# TC264Driver.net
KiCad netlist of a schematic drawn in Altium Designer
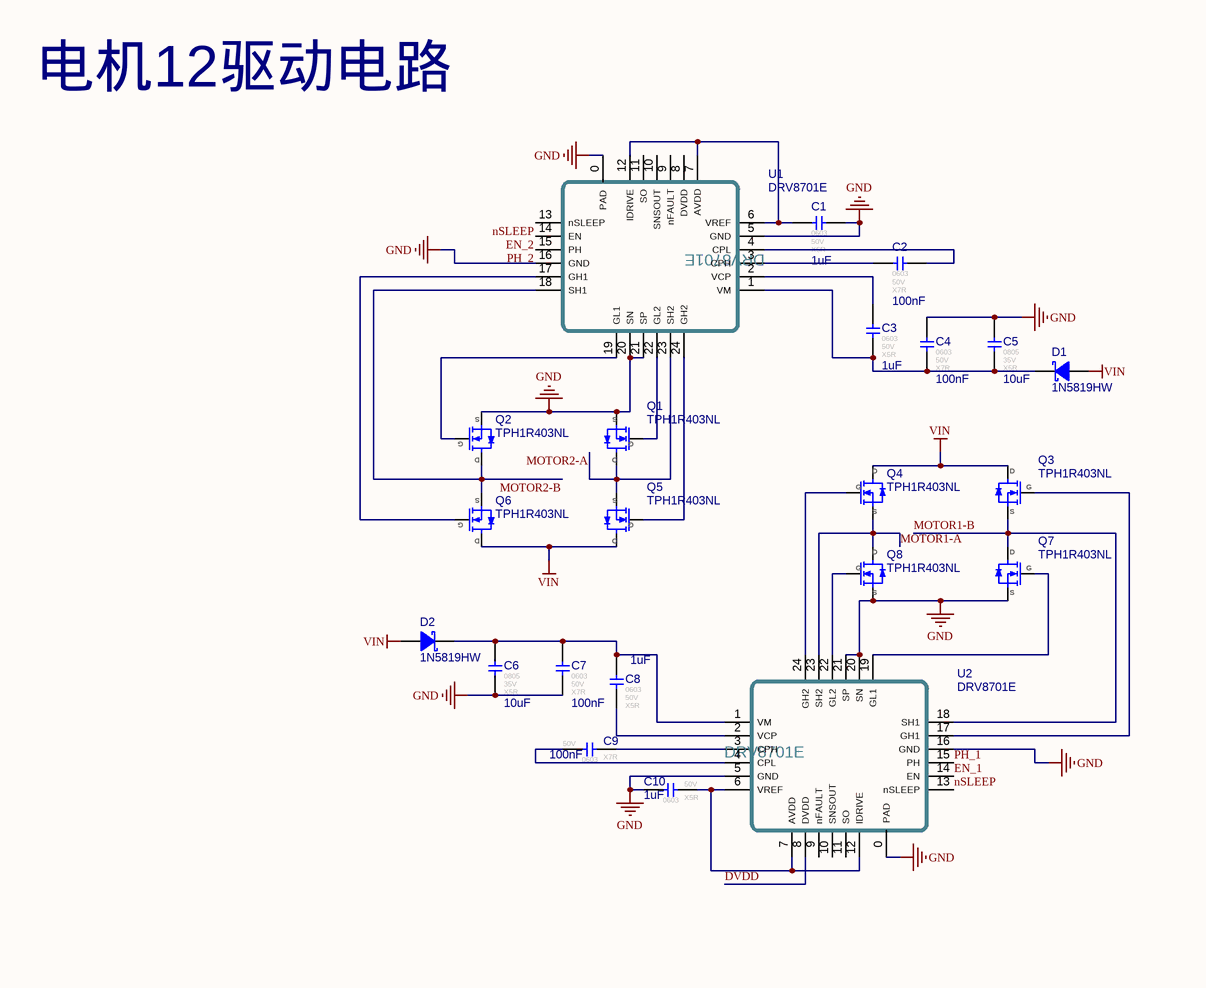
[diagram p0: TC264Driver.SchDoc, top left]
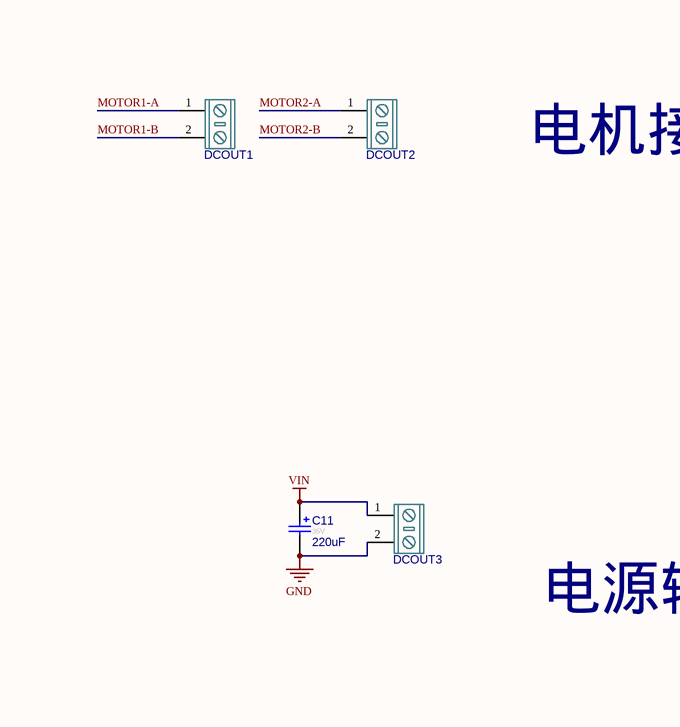
[diagram p1: TC264Driver.SchDoc, top right]
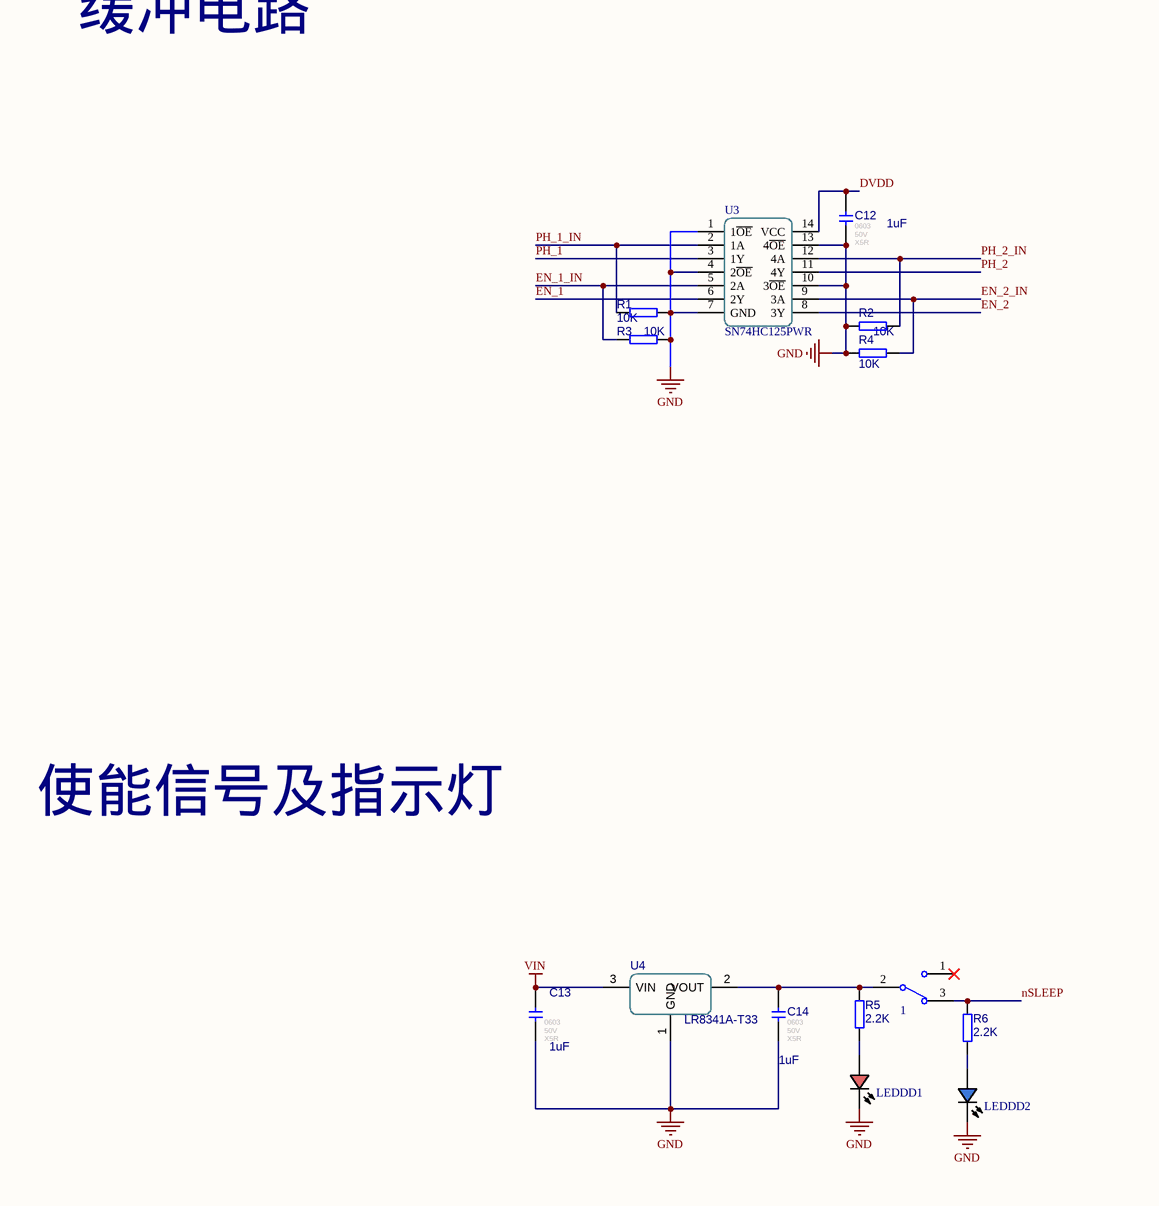
[diagram p2: TC264Driver.SchDoc, bottom left]
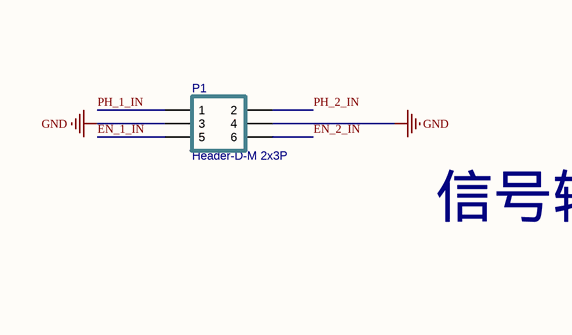
[diagram p3: TC264Driver.SchDoc, bottom right]

(export (version "E")
  (design (tool "Eeschema 10.0.6"))
  (components
    (comp (ref "1")
      (value "SW-SPDT")
      (footprint "SS12D10")
      (description "单刀双掷开关 3脚船型、钮子、拨动开关 SPDT Subminiature Toggle Switch")
      (fields (field (name "PUBLISHER") "Altium Limited"))
      (libsource (lib "TC264") (part "SW-SPDT_1"))
    )
    (comp (ref "C1")
      (value "1uF")
      (footprint "0603")
      (description "贴片瓷片电容; MLCC; 0603(1608);")
      (fields
        (field (name "VOLTAGE") "50V")
        (field (name "TYPE") "X5R")
        (field (name "Comment") "1uF 50V X5R")
      )
      (libsource (lib "TC264") (part "1uF 0603 50V X5R"))
    )
    (comp (ref "C2")
      (value "100nF")
      (footprint "0603")
      (description "贴片瓷片电容; MLCC; 0603(1608);")
      (fields
        (field (name "VOLTAGE") "50V")
        (field (name "TYPE") "X7R")
        (field (name "Comment") "100nF 50V X7R")
      )
      (libsource (lib "TC264") (part "100nF 0603 50V X7R"))
    )
    (comp (ref "C3")
      (value "1uF")
      (footprint "0603")
      (description "贴片瓷片电容; MLCC; 0603(1608);")
      (fields
        (field (name "VOLTAGE") "50V")
        (field (name "TYPE") "X5R")
        (field (name "Comment") "1uF 50V X5R")
      )
      (libsource (lib "TC264") (part "1uF 0603 50V X5R"))
    )
    (comp (ref "C4")
      (value "100nF")
      (footprint "0603")
      (description "贴片瓷片电容; MLCC; 0603(1608);")
      (fields
        (field (name "VOLTAGE") "50V")
        (field (name "TYPE") "X7R")
        (field (name "Comment") "100nF 50V X7R")
      )
      (libsource (lib "TC264") (part "100nF 0603 50V X7R"))
    )
    (comp (ref "C5")
      (value "10uF")
      (footprint "0805")
      (description "贴片瓷片电容; MLCC; 0805(2012);")
      (fields
        (field (name "VOLTAGE") "35V")
        (field (name "TYPE") "X5R")
        (field (name "Comment") "10uF 35V X5R")
      )
      (libsource (lib "TC264") (part "10uF 0805 35V X5R"))
    )
    (comp (ref "C6")
      (value "10uF")
      (footprint "0805")
      (description "贴片瓷片电容; MLCC; 0805(2012);")
      (fields
        (field (name "VOLTAGE") "35V")
        (field (name "TYPE") "X5R")
        (field (name "Comment") "10uF 35V X5R")
      )
      (libsource (lib "TC264") (part "10uF 0805 35V X5R"))
    )
    (comp (ref "C7")
      (value "100nF")
      (footprint "0603")
      (description "贴片瓷片电容; MLCC; 0603(1608);")
      (fields
        (field (name "VOLTAGE") "50V")
        (field (name "TYPE") "X7R")
        (field (name "Comment") "100nF 50V X7R")
      )
      (libsource (lib "TC264") (part "100nF 0603 50V X7R"))
    )
    (comp (ref "C8")
      (value "1uF")
      (footprint "0603")
      (description "贴片瓷片电容; MLCC; 0603(1608);")
      (fields
        (field (name "VOLTAGE") "50V")
        (field (name "TYPE") "X5R")
        (field (name "Comment") "1uF 50V X5R")
      )
      (libsource (lib "TC264") (part "1uF 0603 50V X5R"))
    )
    (comp (ref "C9")
      (value "100nF")
      (footprint "0603")
      (description "贴片瓷片电容; MLCC; 0603(1608);")
      (fields
        (field (name "VOLTAGE") "50V")
        (field (name "TYPE") "X7R")
        (field (name "Comment") "100nF 50V X7R")
      )
      (libsource (lib "TC264") (part "100nF 0603 50V X7R"))
    )
    (comp (ref "C10")
      (value "1uF")
      (footprint "0603")
      (description "贴片瓷片电容; MLCC; 0603(1608);")
      (fields
        (field (name "VOLTAGE") "50V")
        (field (name "TYPE") "X5R")
        (field (name "Comment") "1uF 50V X5R")
      )
      (libsource (lib "TC264") (part "1uF 0603 50V X5R"))
    )
    (comp (ref "C11")
      (value "220uF")
      (footprint "Cap-S-D 3.5-8x11.5")
      (description "直插固态电容 220uF 35V 8x12")
      (fields (field (name "VOLTAGE") "35V") (field (name "Comment") "220uF 35V 聚合物固态"))
      (libsource (lib "TC264") (part "S-D 220uF 35V 8x12"))
    )
    (comp (ref "C12")
      (value "1uF")
      (footprint "0603")
      (description "贴片瓷片电容; MLCC; 0603(1608);")
      (fields
        (field (name "VOLTAGE") "50V")
        (field (name "TYPE") "X5R")
        (field (name "Comment") "1uF 50V X5R")
      )
      (libsource (lib "TC264") (part "1uF 0603 50V X5R"))
    )
    (comp (ref "C13")
      (value "1uF")
      (footprint "0603")
      (description "贴片瓷片电容; MLCC; 0603(1608);")
      (fields
        (field (name "VOLTAGE") "50V")
        (field (name "TYPE") "X5R")
        (field (name "Comment") "1uF 50V X5R")
      )
      (libsource (lib "TC264") (part "1uF 0603 50V X5R"))
    )
    (comp (ref "C14")
      (value "1uF")
      (footprint "0603")
      (description "贴片瓷片电容; MLCC; 0603(1608);")
      (fields
        (field (name "VOLTAGE") "50V")
        (field (name "TYPE") "X5R")
        (field (name "Comment") "1uF 50V X5R")
      )
      (libsource (lib "TC264") (part "1uF 0603 50V X5R"))
    )
    (comp (ref "D1")
      (value "1N5819HW")
      (footprint "SOD-123-L")
      (description "1N5819HW 肖特基二极管")
      (libsource (lib "TC264") (part "1N5819HW"))
    )
    (comp (ref "D2")
      (value "1N5819HW")
      (footprint "SOD-123-L")
      (description "1N5819HW 肖特基二极管")
      (libsource (lib "TC264") (part "1N5819HW"))
    )
    (comp (ref "DCOUT1")
      (value "KF/WJ/DG 30x connecter")
      (footprint "KF/WJ/DG 301-2p-5.0mm")
      (description "接线端子 2Pin")
      (libsource (lib "TC264") (part "KF/WJ/DG 30x"))
    )
    (comp (ref "DCOUT2")
      (value "KF/WJ/DG 30x connecter")
      (footprint "KF/WJ/DG 301-2p-5.0mm")
      (description "接线端子 2Pin")
      (libsource (lib "TC264") (part "KF/WJ/DG 30x"))
    )
    (comp (ref "DCOUT3")
      (value "KF/WJ/DG 30x connecter")
      (footprint "KF/WJ/DG 301-2p-5.0mm")
      (description "接线端子 2Pin")
      (libsource (lib "TC264") (part "KF/WJ/DG 30x"))
    )
    (comp (ref "LEDDD1")
      (value "红色贴片LED")
      (footprint "LEDC1608(0603)-L")
      (fields (field (name "PUBLISHER") "Altium Limited"))
      (libsource (lib "TC264") (part "LED Chip Red"))
    )
    (comp (ref "LEDDD2")
      (value "蓝色贴片LED")
      (footprint "LEDC1608(0603)-L")
      (fields (field (name "PUBLISHER") "Altium Limited"))
      (libsource (lib "TC264") (part "LED Chip Blue"))
    )
    (comp (ref "P1")
      (value "Header-D-M 2x3P")
      (footprint "HDR2X3-M")
      (description "2x3pin, 直插, 双排针")
      (libsource (lib "TC264") (part "Header-D-M 2x3P"))
    )
    (comp (ref "Q1")
      (value "TPH1R403NL")
      (footprint "DFN5x6")
      (description "东芝 N沟 MOS")
      (libsource (lib "TC264") (part "TPH1R403NL"))
    )
    (comp (ref "Q2")
      (value "TPH1R403NL")
      (footprint "DFN5x6")
      (description "东芝 N沟 MOS")
      (libsource (lib "TC264") (part "TPH1R403NL"))
    )
    (comp (ref "Q3")
      (value "TPH1R403NL")
      (footprint "DFN5x6")
      (description "东芝 N沟 MOS")
      (libsource (lib "TC264") (part "TPH1R403NL"))
    )
    (comp (ref "Q4")
      (value "TPH1R403NL")
      (footprint "DFN5x6")
      (description "东芝 N沟 MOS")
      (libsource (lib "TC264") (part "TPH1R403NL"))
    )
    (comp (ref "Q5")
      (value "TPH1R403NL")
      (footprint "DFN5x6")
      (description "东芝 N沟 MOS")
      (libsource (lib "TC264") (part "TPH1R403NL"))
    )
    (comp (ref "Q6")
      (value "TPH1R403NL")
      (footprint "DFN5x6")
      (description "东芝 N沟 MOS")
      (libsource (lib "TC264") (part "TPH1R403NL"))
    )
    (comp (ref "Q7")
      (value "TPH1R403NL")
      (footprint "DFN5x6")
      (description "东芝 N沟 MOS")
      (libsource (lib "TC264") (part "TPH1R403NL"))
    )
    (comp (ref "Q8")
      (value "TPH1R403NL")
      (footprint "DFN5x6")
      (description "东芝 N沟 MOS")
      (libsource (lib "TC264") (part "TPH1R403NL"))
    )
    (comp (ref "R1")
      (value "10K")
      (footprint "RESC1608[0603]S-L")
      (description "贴片电阻")
      (fields (field (name "TOLERANCE") "±1%") (field (name "Comment") "10K ±1%"))
      (libsource (lib "TC264") (part "Res-Chip_12"))
    )
    (comp (ref "R2")
      (value "10K")
      (footprint "RESC1608[0603]S-L")
      (description "贴片电阻")
      (fields (field (name "TOLERANCE") "±1%") (field (name "Comment") "10K ±1%"))
      (libsource (lib "TC264") (part "Res-Chip_12"))
    )
    (comp (ref "R3")
      (value "10K")
      (footprint "RESC1608[0603]S-L")
      (description "贴片电阻")
      (fields (field (name "TOLERANCE") "±1%") (field (name "Comment") "10K ±1%"))
      (libsource (lib "TC264") (part "Res-Chip_12"))
    )
    (comp (ref "R4")
      (value "10K")
      (footprint "RESC1608[0603]S-L")
      (description "贴片电阻")
      (fields (field (name "TOLERANCE") "±1%") (field (name "Comment") "10K ±1%"))
      (libsource (lib "TC264") (part "Res-Chip_12"))
    )
    (comp (ref "R5")
      (value "2.2K")
      (footprint "RESC1608[0603]S-L")
      (description "贴片电阻")
      (fields (field (name "TOLERANCE") "±1%") (field (name "Comment") "2.2K ±1%"))
      (libsource (lib "TC264") (part "Res-Chip_1_1"))
    )
    (comp (ref "R6")
      (value "2.2K")
      (footprint "RESC1608[0603]S-L")
      (description "贴片电阻")
      (fields (field (name "TOLERANCE") "±1%") (field (name "Comment") "2.2K ±1%"))
      (libsource (lib "TC264") (part "Res-Chip_1_1"))
    )
    (comp (ref "U1")
      (value "DRV8701E")
      (footprint "QFN24-4x4")
      (description "DRV8701E Ti全桥驱动芯片")
      (libsource (lib "TC264") (part "DRV8701E"))
    )
    (comp (ref "U2")
      (value "DRV8701E")
      (footprint "QFN24-4x4")
      (description "DRV8701E Ti全桥驱动芯片")
      (libsource (lib "TC264") (part "DRV8701E"))
    )
    (comp (ref "U3")
      (value "SN74HC125PWR")
      (footprint "TSSOP-14")
      (description "三态输出的四路缓冲器 TSSOP-20")
      (libsource (lib "TC264") (part "SN74HC125PWR"))
    )
    (comp (ref "U4")
      (value "LR8341A-T33")
      (footprint "SOT-23")
      (description "LDO Vin:40V  Vout:3.3V 100mA ±1% 55dB")
      (libsource (lib "TC264") (part "LR8341A-T33"))
    )
  )
  (nets
    (net (code "1") (name "/DVDD") (class "Default")
      (node (ref "C12") (pin "1") (pinfunction "1_1") (pintype "passive"))
      (node (ref "U2") (pin "8") (pinfunction "DVDD_8") (pintype "passive"))
      (node (ref "U3") (pin "14") (pinfunction "VCC_14") (pintype "passive"))
    )
    (net (code "2") (name "/EN_1") (class "Default")
      (node (ref "U2") (pin "14") (pinfunction "EN_14") (pintype "passive"))
      (node (ref "U3") (pin "6") (pinfunction "2Y_6") (pintype "passive"))
    )
    (net (code "3") (name "/EN_1_IN") (class "Default")
      (node (ref "P1") (pin "5") (pinfunction "5_5") (pintype "passive"))
      (node (ref "R3") (pin "1") (pinfunction "1_1") (pintype "passive"))
      (node (ref "U3") (pin "5") (pinfunction "2A_5") (pintype "passive"))
    )
    (net (code "4") (name "/EN_2") (class "Default")
      (node (ref "U1") (pin "14") (pinfunction "EN_14") (pintype "passive"))
      (node (ref "U3") (pin "8") (pinfunction "3Y_8") (pintype "passive"))
    )
    (net (code "5") (name "/EN_2_IN") (class "Default")
      (node (ref "P1") (pin "6") (pinfunction "6_6") (pintype "passive"))
      (node (ref "R4") (pin "1") (pinfunction "1_1") (pintype "passive"))
      (node (ref "U3") (pin "9") (pinfunction "3A_9") (pintype "passive"))
    )
    (net (code "6") (name "/MOTOR1-A") (class "Default")
      (node (ref "DCOUT1") (pin "1") (pinfunction "1_1") (pintype "passive"))
      (node (ref "Q4") (pin "3") (pinfunction "S_3") (pintype "passive"))
      (node (ref "Q8") (pin "1") (pinfunction "D_1") (pintype "passive"))
      (node (ref "U2") (pin "23") (pinfunction "SH2_23") (pintype "passive"))
    )
    (net (code "7") (name "/MOTOR1-B") (class "Default")
      (node (ref "DCOUT1") (pin "2") (pinfunction "2_2") (pintype "passive"))
      (node (ref "Q3") (pin "3") (pinfunction "S_3") (pintype "passive"))
      (node (ref "Q7") (pin "1") (pinfunction "D_1") (pintype "passive"))
      (node (ref "U2") (pin "18") (pinfunction "SH1_18") (pintype "passive"))
    )
    (net (code "8") (name "/MOTOR2-A") (class "Default")
      (node (ref "DCOUT2") (pin "1") (pinfunction "1_1") (pintype "passive"))
      (node (ref "Q1") (pin "1") (pinfunction "D_1") (pintype "passive"))
      (node (ref "Q5") (pin "3") (pinfunction "S_3") (pintype "passive"))
      (node (ref "U1") (pin "23") (pinfunction "SH2_23") (pintype "passive"))
    )
    (net (code "9") (name "/MOTOR2-B") (class "Default")
      (node (ref "DCOUT2") (pin "2") (pinfunction "2_2") (pintype "passive"))
      (node (ref "Q2") (pin "1") (pinfunction "D_1") (pintype "passive"))
      (node (ref "Q6") (pin "3") (pinfunction "S_3") (pintype "passive"))
      (node (ref "U1") (pin "18") (pinfunction "SH1_18") (pintype "passive"))
    )
    (net (code "10") (name "/PH_1") (class "Default")
      (node (ref "U2") (pin "15") (pinfunction "PH_15") (pintype "passive"))
      (node (ref "U3") (pin "3") (pinfunction "1Y_3") (pintype "passive"))
    )
    (net (code "11") (name "/PH_1_IN") (class "Default")
      (node (ref "P1") (pin "1") (pinfunction "1_1") (pintype "passive"))
      (node (ref "R1") (pin "1") (pinfunction "1_1") (pintype "passive"))
      (node (ref "U3") (pin "2") (pinfunction "1A_2") (pintype "passive"))
    )
    (net (code "12") (name "/PH_2") (class "Default")
      (node (ref "U1") (pin "15") (pinfunction "PH_15") (pintype "passive"))
      (node (ref "U3") (pin "11") (pinfunction "4Y_11") (pintype "passive"))
    )
    (net (code "13") (name "/PH_2_IN") (class "Default")
      (node (ref "P1") (pin "2") (pinfunction "2_2") (pintype "passive"))
      (node (ref "R2") (pin "1") (pinfunction "1_1") (pintype "passive"))
      (node (ref "U3") (pin "12") (pinfunction "4A_12") (pintype "passive"))
    )
    (net (code "14") (name "/nSLEEP") (class "Default")
      (node (ref "1") (pin "3") (pintype "passive"))
      (node (ref "R6") (pin "2") (pinfunction "2_2") (pintype "passive"))
      (node (ref "U1") (pin "13") (pinfunction "nSLEEP_13") (pintype "passive"))
      (node (ref "U2") (pin "13") (pinfunction "nSLEEP_13") (pintype "passive"))
    )
    (net (code "15") (name "GND") (class "Default")
      (node (ref "C1") (pin "2") (pinfunction "2_2") (pintype "passive"))
      (node (ref "C10") (pin "2") (pinfunction "2_2") (pintype "passive"))
      (node (ref "C11") (pin "2") (pinfunction "2_2") (pintype "passive"))
      (node (ref "C12") (pin "2") (pinfunction "2_2") (pintype "passive"))
      (node (ref "C13") (pin "2") (pinfunction "2_2") (pintype "passive"))
      (node (ref "C14") (pin "2") (pinfunction "2_2") (pintype "passive"))
      (node (ref "C4") (pin "1") (pinfunction "1_1") (pintype "passive"))
      (node (ref "C5") (pin "1") (pinfunction "1_1") (pintype "passive"))
      (node (ref "C6") (pin "1") (pinfunction "1_1") (pintype "passive"))
      (node (ref "C7") (pin "1") (pinfunction "1_1") (pintype "passive"))
      (node (ref "DCOUT3") (pin "2") (pinfunction "2_2") (pintype "passive"))
      (node (ref "LEDDD1") (pin "C") (pinfunction "C_C") (pintype "passive"))
      (node (ref "LEDDD2") (pin "C") (pinfunction "C_C") (pintype "passive"))
      (node (ref "P1") (pin "3") (pinfunction "3_3") (pintype "passive"))
      (node (ref "P1") (pin "4") (pinfunction "4_4") (pintype "passive"))
      (node (ref "Q1") (pin "3") (pinfunction "S_3") (pintype "passive"))
      (node (ref "Q2") (pin "3") (pinfunction "S_3") (pintype "passive"))
      (node (ref "Q7") (pin "3") (pinfunction "S_3") (pintype "passive"))
      (node (ref "Q8") (pin "3") (pinfunction "S_3") (pintype "passive"))
      (node (ref "R1") (pin "2") (pinfunction "2_2") (pintype "passive"))
      (node (ref "R2") (pin "2") (pinfunction "2_2") (pintype "passive"))
      (node (ref "R3") (pin "2") (pinfunction "2_2") (pintype "passive"))
      (node (ref "R4") (pin "2") (pinfunction "2_2") (pintype "passive"))
      (node (ref "U1") (pin "0") (pinfunction "PAD_0") (pintype "passive"))
      (node (ref "U1") (pin "16") (pinfunction "GND_16") (pintype "passive"))
      (node (ref "U1") (pin "20") (pinfunction "SN_20") (pintype "passive"))
      (node (ref "U1") (pin "21") (pinfunction "SP_21") (pintype "passive"))
      (node (ref "U1") (pin "5") (pinfunction "GND_5") (pintype "passive"))
      (node (ref "U2") (pin "0") (pinfunction "PAD_0") (pintype "passive"))
      (node (ref "U2") (pin "16") (pinfunction "GND_16") (pintype "passive"))
      (node (ref "U2") (pin "20") (pinfunction "SN_20") (pintype "passive"))
      (node (ref "U2") (pin "21") (pinfunction "SP_21") (pintype "passive"))
      (node (ref "U2") (pin "5") (pinfunction "GND_5") (pintype "passive"))
      (node (ref "U3") (pin "1") (pinfunction "1~{OE}_1") (pintype "passive"))
      (node (ref "U3") (pin "10") (pinfunction "3~{OE}_10") (pintype "passive"))
      (node (ref "U3") (pin "13") (pinfunction "4~{OE}_13") (pintype "passive"))
      (node (ref "U3") (pin "4") (pinfunction "2~{OE}_4") (pintype "passive"))
      (node (ref "U3") (pin "7") (pinfunction "GND_7") (pintype "passive"))
      (node (ref "U4") (pin "1") (pinfunction "GND_1") (pintype "passive"))
    )
    (net (code "16") (name "Net-(LEDDD1-PadA)") (class "Default")
      (node (ref "LEDDD1") (pin "A") (pinfunction "A_A") (pintype "passive"))
      (node (ref "R5") (pin "1") (pinfunction "1_1") (pintype "passive"))
    )
    (net (code "17") (name "Net-(LEDDD2-PadA)") (class "Default")
      (node (ref "LEDDD2") (pin "A") (pinfunction "A_A") (pintype "passive"))
      (node (ref "R6") (pin "1") (pinfunction "1_1") (pintype "passive"))
    )
    (net (code "18") (name "Net-(Q1-G)") (class "Default")
      (node (ref "Q1") (pin "2") (pinfunction "G_2") (pintype "passive"))
      (node (ref "U1") (pin "22") (pinfunction "GL2_22") (pintype "passive"))
    )
    (net (code "19") (name "Net-(Q2-G)") (class "Default")
      (node (ref "Q2") (pin "2") (pinfunction "G_2") (pintype "passive"))
      (node (ref "U1") (pin "19") (pinfunction "GL1_19") (pintype "passive"))
    )
    (net (code "20") (name "Net-(Q3-G)") (class "Default")
      (node (ref "Q3") (pin "2") (pinfunction "G_2") (pintype "passive"))
      (node (ref "U2") (pin "17") (pinfunction "GH1_17") (pintype "passive"))
    )
    (net (code "21") (name "Net-(Q4-G)") (class "Default")
      (node (ref "Q4") (pin "2") (pinfunction "G_2") (pintype "passive"))
      (node (ref "U2") (pin "24") (pinfunction "GH2_24") (pintype "passive"))
    )
    (net (code "22") (name "Net-(Q5-G)") (class "Default")
      (node (ref "Q5") (pin "2") (pinfunction "G_2") (pintype "passive"))
      (node (ref "U1") (pin "24") (pinfunction "GH2_24") (pintype "passive"))
    )
    (net (code "23") (name "Net-(Q6-G)") (class "Default")
      (node (ref "Q6") (pin "2") (pinfunction "G_2") (pintype "passive"))
      (node (ref "U1") (pin "17") (pinfunction "GH1_17") (pintype "passive"))
    )
    (net (code "24") (name "Net-(Q7-G)") (class "Default")
      (node (ref "Q7") (pin "2") (pinfunction "G_2") (pintype "passive"))
      (node (ref "U2") (pin "19") (pinfunction "GL1_19") (pintype "passive"))
    )
    (net (code "25") (name "Net-(Q8-G)") (class "Default")
      (node (ref "Q8") (pin "2") (pinfunction "G_2") (pintype "passive"))
      (node (ref "U2") (pin "22") (pinfunction "GL2_22") (pintype "passive"))
    )
    (net (code "26") (name "Net-(U1-AVDD)") (class "Default")
      (node (ref "C1") (pin "1") (pinfunction "1_1") (pintype "passive"))
      (node (ref "U1") (pin "12") (pinfunction "IDRIVE_12") (pintype "passive"))
      (node (ref "U1") (pin "6") (pinfunction "VREF_6") (pintype "passive"))
      (node (ref "U1") (pin "7") (pinfunction "AVDD_7") (pintype "passive"))
    )
    (net (code "27") (name "Net-(U1-CPH)") (class "Default")
      (node (ref "C2") (pin "1") (pinfunction "1_1") (pintype "passive"))
      (node (ref "U1") (pin "3") (pinfunction "CPH_3") (pintype "passive"))
    )
    (net (code "28") (name "Net-(U1-CPL)") (class "Default")
      (node (ref "C2") (pin "2") (pinfunction "2_2") (pintype "passive"))
      (node (ref "U1") (pin "4") (pinfunction "CPL_4") (pintype "passive"))
    )
    (net (code "29") (name "Net-(U1-VCP)") (class "Default")
      (node (ref "C3") (pin "1") (pinfunction "1_1") (pintype "passive"))
      (node (ref "U1") (pin "2") (pinfunction "VCP_2") (pintype "passive"))
    )
    (net (code "30") (name "Net-(U1-VM)") (class "Default")
      (node (ref "C3") (pin "2") (pinfunction "2_2") (pintype "passive"))
      (node (ref "C4") (pin "2") (pinfunction "2_2") (pintype "passive"))
      (node (ref "C5") (pin "2") (pinfunction "2_2") (pintype "passive"))
      (node (ref "D1") (pin "K") (pinfunction "K_K") (pintype "passive"))
      (node (ref "U1") (pin "1") (pinfunction "VM_1") (pintype "passive"))
    )
    (net (code "31") (name "Net-(U2-AVDD)") (class "Default")
      (node (ref "C10") (pin "1") (pinfunction "1_1") (pintype "passive"))
      (node (ref "U2") (pin "12") (pinfunction "IDRIVE_12") (pintype "passive"))
      (node (ref "U2") (pin "6") (pinfunction "VREF_6") (pintype "passive"))
      (node (ref "U2") (pin "7") (pinfunction "AVDD_7") (pintype "passive"))
    )
    (net (code "32") (name "Net-(U2-CPH)") (class "Default")
      (node (ref "C9") (pin "1") (pinfunction "1_1") (pintype "passive"))
      (node (ref "U2") (pin "3") (pinfunction "CPH_3") (pintype "passive"))
    )
    (net (code "33") (name "Net-(U2-CPL)") (class "Default")
      (node (ref "C9") (pin "2") (pinfunction "2_2") (pintype "passive"))
      (node (ref "U2") (pin "4") (pinfunction "CPL_4") (pintype "passive"))
    )
    (net (code "34") (name "Net-(U2-VCP)") (class "Default")
      (node (ref "C8") (pin "1") (pinfunction "1_1") (pintype "passive"))
      (node (ref "U2") (pin "2") (pinfunction "VCP_2") (pintype "passive"))
    )
    (net (code "35") (name "Net-(U2-VM)") (class "Default")
      (node (ref "C6") (pin "2") (pinfunction "2_2") (pintype "passive"))
      (node (ref "C7") (pin "2") (pinfunction "2_2") (pintype "passive"))
      (node (ref "C8") (pin "2") (pinfunction "2_2") (pintype "passive"))
      (node (ref "D2") (pin "K") (pinfunction "K_K") (pintype "passive"))
      (node (ref "U2") (pin "1") (pinfunction "VM_1") (pintype "passive"))
    )
    (net (code "36") (name "Net-(U4-VOUT)") (class "Default")
      (node (ref "1") (pin "2") (pintype "passive"))
      (node (ref "C14") (pin "1") (pinfunction "1_1") (pintype "passive"))
      (node (ref "R5") (pin "2") (pinfunction "2_2") (pintype "passive"))
      (node (ref "U4") (pin "2") (pinfunction "VOUT_2") (pintype "passive"))
    )
    (net (code "37") (name "VIN") (class "Default")
      (node (ref "C11") (pin "1") (pinfunction "1_1") (pintype "passive"))
      (node (ref "C13") (pin "1") (pinfunction "1_1") (pintype "passive"))
      (node (ref "D1") (pin "A") (pinfunction "A_A") (pintype "passive"))
      (node (ref "D2") (pin "A") (pinfunction "A_A") (pintype "passive"))
      (node (ref "DCOUT3") (pin "1") (pinfunction "1_1") (pintype "passive"))
      (node (ref "Q3") (pin "1") (pinfunction "D_1") (pintype "passive"))
      (node (ref "Q4") (pin "1") (pinfunction "D_1") (pintype "passive"))
      (node (ref "Q5") (pin "1") (pinfunction "D_1") (pintype "passive"))
      (node (ref "Q6") (pin "1") (pinfunction "D_1") (pintype "passive"))
      (node (ref "U4") (pin "3") (pinfunction "VIN_3") (pintype "passive"))
    )
    (net (code "38") (name "unconnected-(1-Pad1)") (class "Default")
      (node (ref "1") (pin "1") (pintype "passive+no_connect"))
    )
    (net (code "39") (name "unconnected-(U1-DVDD-Pad8)") (class "Default")
      (node (ref "U1") (pin "8") (pinfunction "DVDD_8") (pintype "passive"))
    )
    (net (code "40") (name "unconnected-(U1-SNSOUT-Pad10)") (class "Default")
      (node (ref "U1") (pin "10") (pinfunction "SNSOUT_10") (pintype "passive"))
    )
    (net (code "41") (name "unconnected-(U1-SO-Pad11)") (class "Default")
      (node (ref "U1") (pin "11") (pinfunction "SO_11") (pintype "passive"))
    )
    (net (code "42") (name "unconnected-(U1-nFAULT-Pad9)") (class "Default")
      (node (ref "U1") (pin "9") (pinfunction "nFAULT_9") (pintype "passive"))
    )
    (net (code "43") (name "unconnected-(U2-SNSOUT-Pad10)") (class "Default")
      (node (ref "U2") (pin "10") (pinfunction "SNSOUT_10") (pintype "passive"))
    )
    (net (code "44") (name "unconnected-(U2-SO-Pad11)") (class "Default")
      (node (ref "U2") (pin "11") (pinfunction "SO_11") (pintype "passive"))
    )
    (net (code "45") (name "unconnected-(U2-nFAULT-Pad9)") (class "Default")
      (node (ref "U2") (pin "9") (pinfunction "nFAULT_9") (pintype "passive"))
    )
  )
)
